# TR.net
KiCad netlist of a schematic drawn in Altium Designer
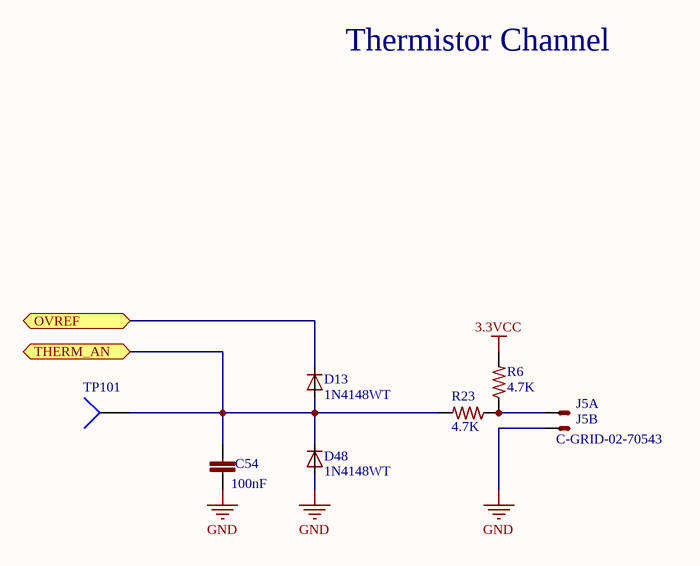
[diagram p0: TR.SchDoc]

(export (version "E")
  (design (tool "Eeschema 10.0.6"))
  (components
    (comp (ref "C54")
      (value "100nF")
      (footprint "C0402")
      (description "CAP CER 0402 100nF 16V 10% X7R")
      (fields
        (field (name "MANUFACTURERPARTNUMBER") "GRM155R71C104KA88D")
        (field (name "PUBLISHER") "UltiMachine")
      )
      (libsource (lib "3Delight") (part "GRM155R71C104KA88D"))
    )
    (comp (ref "D13")
      (value "1N4148WT")
      (footprint "SOD523")
      (description "DIODE SOD523")
      (fields (field (name "PUBLISHER") "UltiMachine"))
      (libsource (lib "3Delight") (part "1N4148WT"))
    )
    (comp (ref "D48")
      (value "1N4148WT")
      (footprint "SOD523")
      (description "DIODE SOD523")
      (fields (field (name "PUBLISHER") "UltiMachine"))
      (libsource (lib "3Delight") (part "1N4148WT"))
    )
    (comp (ref "J5")
      (value "C-GRID-02-70543")
      (footprint "70543-02")
      (description "Connector 2pos")
      (fields (field (name "PUBLISHER") "UltiMachine"))
      (libsource (lib "3Delight") (part "C-GRID-02-70543"))
    )
    (comp (ref "R6")
      (value "4.7K")
      (footprint "R0603")
      (description "RES 0603 4.7K 100mW 1%")
      (fields (field (name "MANUFACTURERPARTNUMBER") "ERJ3EKF4701V") (field (name "PUBLISHER") "UltiMachine"))
      (libsource (lib "3Delight") (part "ERJ3EKF4701V"))
    )
    (comp (ref "R23")
      (value "4.7K")
      (footprint "R0603")
      (description "RES 0603 4.7K 100mW 1%")
      (fields (field (name "MANUFACTURERPARTNUMBER") "ERJ3EKF4701V") (field (name "PUBLISHER") "UltiMachine"))
      (libsource (lib "3Delight") (part "ERJ3EKF4701V"))
    )
    (comp (ref "TP101")
      (value "TP4")
      (footprint "TP-2")
      (description "Socket")
      (fields (field (name "PUBLISHER") "Altium Limited"))
      (libsource (lib "ZMBo Schematic Library") (part "Socket"))
    )
  )
  (nets
    (net (code "1") (name "/OVREF") (class "Default")
      (node (ref "D13") (pin "C") (pinfunction "C_C") (pintype "passive"))
    )
    (net (code "2") (name "/THERM_AN") (class "Default")
      (node (ref "C54") (pin "1") (pinfunction "1_1") (pintype "passive"))
      (node (ref "D13") (pin "A") (pinfunction "A_A") (pintype "passive"))
      (node (ref "D48") (pin "C") (pinfunction "C_C") (pintype "passive"))
      (node (ref "R23") (pin "2") (pinfunction "2_2") (pintype "passive"))
      (node (ref "TP101") (pin "1") (pinfunction "1_1") (pintype "passive"))
    )
    (net (code "3") (name "3.3VCC") (class "Default")
      (node (ref "R6") (pin "2") (pinfunction "2_2") (pintype "passive"))
    )
    (net (code "4") (name "GND") (class "Default")
      (node (ref "C54") (pin "2") (pinfunction "2_2") (pintype "passive"))
      (node (ref "D48") (pin "A") (pinfunction "A_A") (pintype "passive"))
      (node (ref "J5") (pin "2") (pinfunction "S_2") (pintype "passive"))
    )
    (net (code "5") (name "Net-(J5A-S)") (class "Default")
      (node (ref "J5") (pin "1") (pinfunction "S_1") (pintype "passive"))
      (node (ref "R23") (pin "1") (pinfunction "1_1") (pintype "passive"))
      (node (ref "R6") (pin "1") (pinfunction "1_1") (pintype "passive"))
    )
  )
)
